# 2_-_IO_Socket_0.net
KiCad netlist of a schematic drawn in Altium Designer
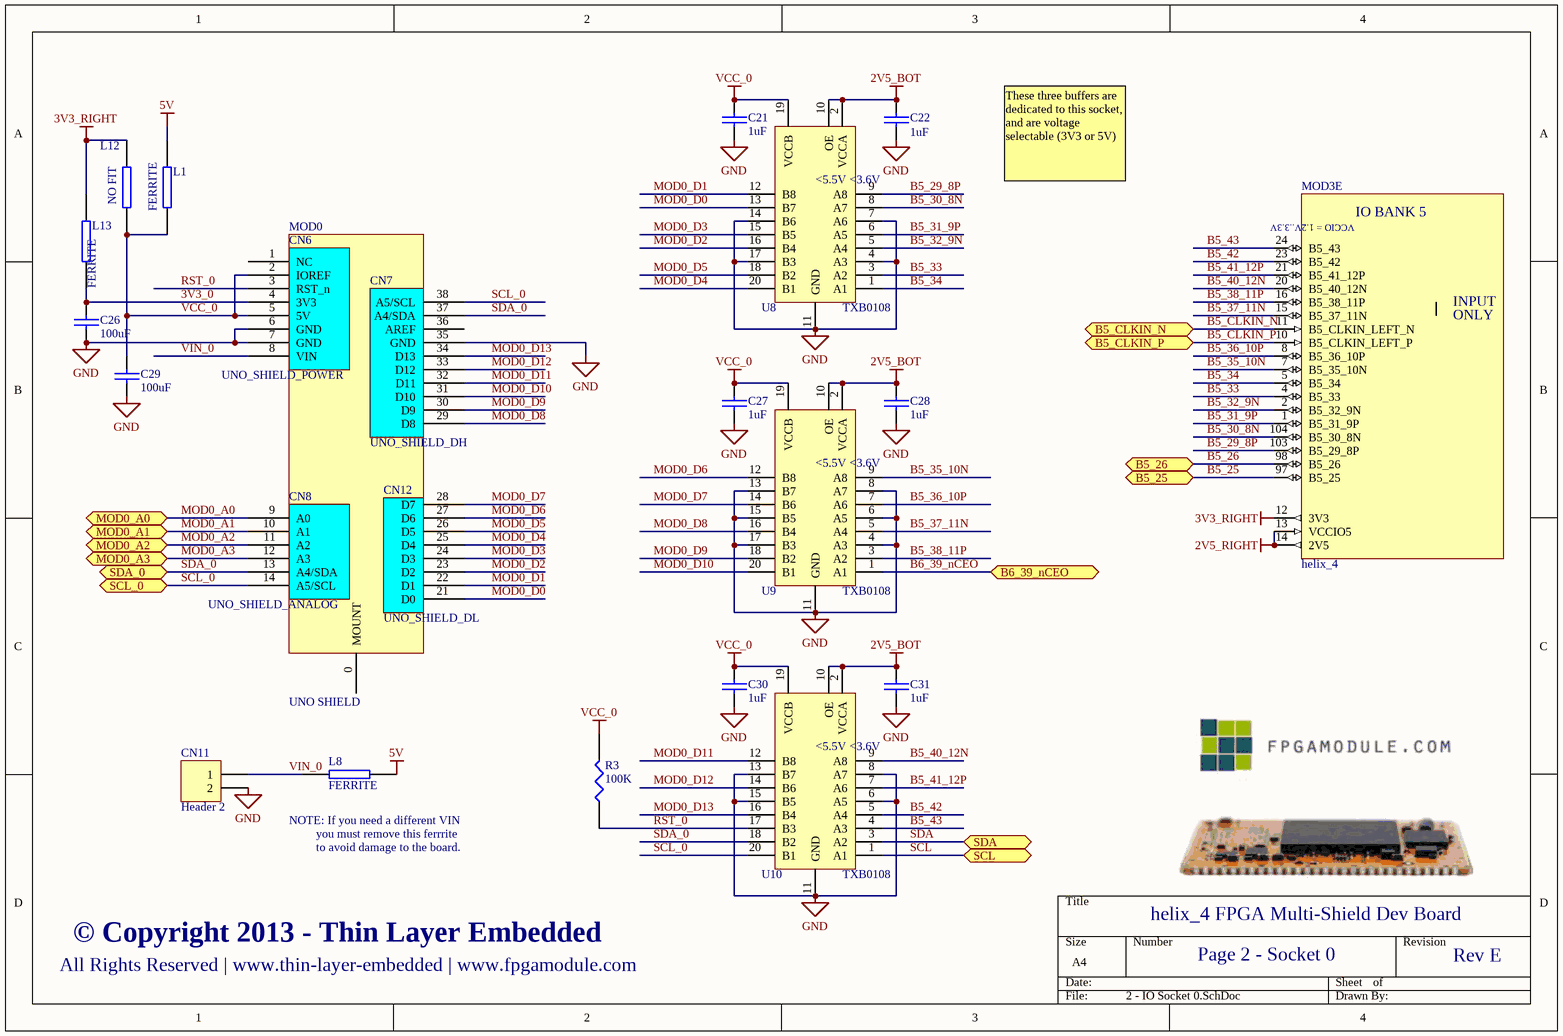
[diagram p0: 2 - IO Socket 0.SchDoc]

(export (version "E")
  (design (tool "Eeschema 10.0.6"))
  (components
    (comp (ref "C21")
      (value "1uF")
      (footprint "0805")
      (description "Capacitor")
      (libsource (lib "*") (part "CAP"))
    )
    (comp (ref "C22")
      (value "1uF")
      (footprint "0805")
      (description "Capacitor")
      (libsource (lib "*") (part "CAP"))
    )
    (comp (ref "C26")
      (value "100uF")
      (footprint "1210")
      (description "Capacitor")
      (libsource (lib "*") (part "CAP"))
    )
    (comp (ref "C27")
      (value "1uF")
      (footprint "0805")
      (description "Capacitor")
      (libsource (lib "*") (part "CAP"))
    )
    (comp (ref "C28")
      (value "1uF")
      (footprint "0805")
      (description "Capacitor")
      (libsource (lib "*") (part "CAP"))
    )
    (comp (ref "C29")
      (value "100uF")
      (footprint "1210")
      (description "Capacitor")
      (libsource (lib "*") (part "CAP"))
    )
    (comp (ref "C30")
      (value "1uF")
      (footprint "0805")
      (description "Capacitor")
      (libsource (lib "*") (part "CAP"))
    )
    (comp (ref "C31")
      (value "1uF")
      (footprint "0805")
      (description "Capacitor")
      (libsource (lib "*") (part "CAP"))
    )
    (comp (ref "CN6")
      (value "UNO_SHIELD_POWER")
      (footprint "UNO_SHIELD_POWER")
      (libsource (lib "master_library") (part "UNO_SHIELD_POWER"))
    )
    (comp (ref "CN7")
      (value "UNO_SHIELD_DH")
      (footprint "UNO_SHIELD_DH")
      (libsource (lib "master_library") (part "UNO_SHIELD_DH"))
    )
    (comp (ref "CN8")
      (value "UNO_SHIELD_ANALOG")
      (footprint "UNO_SHIELD_ANALOG")
      (libsource (lib "master_library") (part "UNO_SHIELD_ANALOG"))
    )
    (comp (ref "CN11")
      (value "Header 2")
      (footprint "HDR1X2")
      (description "Header, 2-Pin")
      (fields (field (name "PUBLISHER") "Altium Limited"))
      (libsource (lib "Miscellaneous Connectors") (part "Header 2"))
    )
    (comp (ref "CN12")
      (value "UNO_SHIELD_DL")
      (footprint "UNO_SHIELD_DL")
      (libsource (lib "master_library") (part "UNO_SHIELD_DL"))
    )
    (comp (ref "L1") (value "FERRITE") (footprint "0805") (libsource (lib "*") (part "FERRITE")))
    (comp (ref "L8") (value "FERRITE") (footprint "0805") (libsource (lib "*") (part "FERRITE")))
    (comp (ref "L12")
      (value "NO FIT")
      (footprint "0805")
      (description "FERRITE")
      (libsource (lib "*") (part "FERRITE"))
    )
    (comp (ref "L13") (value "FERRITE") (footprint "0805") (libsource (lib "*") (part "FERRITE")))
    (comp (ref "MOD0")
      (value "UNO SHIELD")
      (footprint "UNO_SHIELD_MECH")
      (libsource (lib "master_library") (part "UNO_SHIELD_MECH"))
    )
    (comp (ref "MOD3")
      (value "helix_4")
      (footprint "HELIX_4_LCC104_HOST")
      (libsource (lib "master_library") (part "helix_4 Rev C Module"))
    )
    (comp (ref "R3") (value "100K") (footprint "0805") (libsource (lib "*") (part "RES1")))
    (comp (ref "U8")
      (value "TXB0108")
      (footprint "TSSOP20")
      (description "TI Bir-dir buffer")
      (libsource (lib "master_library") (part "TXB0108"))
    )
    (comp (ref "U9")
      (value "TXB0108")
      (footprint "TSSOP20")
      (description "TI Bir-dir buffer")
      (libsource (lib "master_library") (part "TXB0108"))
    )
    (comp (ref "U10")
      (value "TXB0108")
      (footprint "TSSOP20")
      (description "TI Bir-dir buffer")
      (libsource (lib "master_library") (part "TXB0108"))
    )
  )
  (nets
    (net (code "1") (name "/3V3_0") (class "Default")
      (node (ref "C26") (pin "1") (pinfunction "1_1") (pintype "passive"))
      (node (ref "CN6") (pin "4") (pinfunction "3V3_4") (pintype "passive"))
      (node (ref "L13") (pin "2") (pinfunction "2_2") (pintype "passive"))
    )
    (net (code "2") (name "/B5_25") (class "Default")
      (node (ref "MOD3") (pin "97") (pinfunction "B5_25_97") (pintype "bidirectional"))
    )
    (net (code "3") (name "/B5_26") (class "Default")
      (node (ref "MOD3") (pin "98") (pinfunction "B5_26_98") (pintype "bidirectional"))
    )
    (net (code "4") (name "/B5_29_8P") (class "Default")
      (node (ref "MOD3") (pin "103") (pinfunction "B5_29_8P_103") (pintype "bidirectional"))
      (node (ref "U8") (pin "9") (pinfunction "A8_9") (pintype "passive"))
    )
    (net (code "5") (name "/B5_30_8N") (class "Default")
      (node (ref "MOD3") (pin "104") (pinfunction "B5_30_8N_104") (pintype "bidirectional"))
      (node (ref "U8") (pin "8") (pinfunction "A7_8") (pintype "passive"))
    )
    (net (code "6") (name "/B5_31_9P") (class "Default")
      (node (ref "MOD3") (pin "1") (pinfunction "B5_31_9P_1") (pintype "bidirectional"))
      (node (ref "U8") (pin "6") (pinfunction "A5_6") (pintype "passive"))
    )
    (net (code "7") (name "/B5_32_9N") (class "Default")
      (node (ref "MOD3") (pin "2") (pinfunction "B5_32_9N_2") (pintype "bidirectional"))
      (node (ref "U8") (pin "5") (pinfunction "A4_5") (pintype "passive"))
    )
    (net (code "8") (name "/B5_33") (class "Default")
      (node (ref "MOD3") (pin "4") (pinfunction "B5_33_4") (pintype "bidirectional"))
      (node (ref "U8") (pin "3") (pinfunction "A2_3") (pintype "passive"))
    )
    (net (code "9") (name "/B5_34") (class "Default")
      (node (ref "MOD3") (pin "5") (pinfunction "B5_34_5") (pintype "bidirectional"))
      (node (ref "U8") (pin "1") (pinfunction "A1_1") (pintype "passive"))
    )
    (net (code "10") (name "/B5_35_10N") (class "Default")
      (node (ref "MOD3") (pin "7") (pinfunction "B5_35_10N_7") (pintype "bidirectional"))
      (node (ref "U9") (pin "9") (pinfunction "A8_9") (pintype "passive"))
    )
    (net (code "11") (name "/B5_36_10P") (class "Default")
      (node (ref "MOD3") (pin "8") (pinfunction "B5_36_10P_8") (pintype "bidirectional"))
      (node (ref "U9") (pin "7") (pinfunction "A6_7") (pintype "passive"))
    )
    (net (code "12") (name "/B5_37_11N") (class "Default")
      (node (ref "MOD3") (pin "15") (pinfunction "B5_37_11N_15") (pintype "bidirectional"))
      (node (ref "U9") (pin "5") (pinfunction "A4_5") (pintype "passive"))
    )
    (net (code "13") (name "/B5_38_11P") (class "Default")
      (node (ref "MOD3") (pin "16") (pinfunction "B5_38_11P_16") (pintype "bidirectional"))
      (node (ref "U9") (pin "3") (pinfunction "A2_3") (pintype "passive"))
    )
    (net (code "14") (name "/B5_40_12N") (class "Default")
      (node (ref "MOD3") (pin "20") (pinfunction "B5_40_12N_20") (pintype "bidirectional"))
      (node (ref "U10") (pin "9") (pinfunction "A8_9") (pintype "passive"))
    )
    (net (code "15") (name "/B5_41_12P") (class "Default")
      (node (ref "MOD3") (pin "21") (pinfunction "B5_41_12P_21") (pintype "bidirectional"))
      (node (ref "U10") (pin "7") (pinfunction "A6_7") (pintype "passive"))
    )
    (net (code "16") (name "/B5_42") (class "Default")
      (node (ref "MOD3") (pin "23") (pinfunction "B5_42_23") (pintype "bidirectional"))
      (node (ref "U10") (pin "5") (pinfunction "A4_5") (pintype "passive"))
    )
    (net (code "17") (name "/B5_43") (class "Default")
      (node (ref "MOD3") (pin "24") (pinfunction "B5_43_24") (pintype "bidirectional"))
      (node (ref "U10") (pin "4") (pinfunction "A3_4") (pintype "passive"))
    )
    (net (code "18") (name "/B5_CLKIN_N") (class "Default")
      (node (ref "MOD3") (pin "11") (pinfunction "B5_CLKIN_LEFT_N_11") (pintype "input"))
    )
    (net (code "19") (name "/B5_CLKIN_P") (class "Default")
      (node (ref "MOD3") (pin "10") (pinfunction "B5_CLKIN_LEFT_P_10") (pintype "input"))
    )
    (net (code "20") (name "/B6_39_nCEO") (class "Default")
      (node (ref "U9") (pin "1") (pinfunction "A1_1") (pintype "passive"))
    )
    (net (code "21") (name "/MOD0_A0") (class "Default")
      (node (ref "CN8") (pin "9") (pinfunction "A0_9") (pintype "passive"))
    )
    (net (code "22") (name "/MOD0_A1") (class "Default")
      (node (ref "CN8") (pin "10") (pinfunction "A1_10") (pintype "passive"))
    )
    (net (code "23") (name "/MOD0_A2") (class "Default")
      (node (ref "CN8") (pin "11") (pinfunction "A2_11") (pintype "passive"))
    )
    (net (code "24") (name "/MOD0_A3") (class "Default")
      (node (ref "CN8") (pin "12") (pinfunction "A3_12") (pintype "passive"))
    )
    (net (code "25") (name "/MOD0_D0") (class "Default")
      (node (ref "CN12") (pin "21") (pinfunction "D0_21") (pintype "passive"))
      (node (ref "U8") (pin "13") (pinfunction "B7_13") (pintype "passive"))
    )
    (net (code "26") (name "/MOD0_D1") (class "Default")
      (node (ref "CN12") (pin "22") (pinfunction "D1_22") (pintype "passive"))
      (node (ref "U8") (pin "12") (pinfunction "B8_12") (pintype "passive"))
    )
    (net (code "27") (name "/MOD0_D2") (class "Default")
      (node (ref "CN12") (pin "23") (pinfunction "D2_23") (pintype "passive"))
      (node (ref "U8") (pin "16") (pinfunction "B4_16") (pintype "passive"))
    )
    (net (code "28") (name "/MOD0_D3") (class "Default")
      (node (ref "CN12") (pin "24") (pinfunction "D3_24") (pintype "passive"))
      (node (ref "U8") (pin "15") (pinfunction "B5_15") (pintype "passive"))
    )
    (net (code "29") (name "/MOD0_D4") (class "Default")
      (node (ref "CN12") (pin "25") (pinfunction "D4_25") (pintype "passive"))
      (node (ref "U8") (pin "20") (pinfunction "B1_20") (pintype "passive"))
    )
    (net (code "30") (name "/MOD0_D5") (class "Default")
      (node (ref "CN12") (pin "26") (pinfunction "D5_26") (pintype "passive"))
      (node (ref "U8") (pin "18") (pinfunction "B2_18") (pintype "passive"))
    )
    (net (code "31") (name "/MOD0_D6") (class "Default")
      (node (ref "CN12") (pin "27") (pinfunction "D6_27") (pintype "passive"))
      (node (ref "U9") (pin "12") (pinfunction "B8_12") (pintype "passive"))
    )
    (net (code "32") (name "/MOD0_D7") (class "Default")
      (node (ref "CN12") (pin "28") (pinfunction "D7_28") (pintype "passive"))
      (node (ref "U9") (pin "14") (pinfunction "B6_14") (pintype "passive"))
    )
    (net (code "33") (name "/MOD0_D8") (class "Default")
      (node (ref "CN7") (pin "29") (pinfunction "D8_29") (pintype "passive"))
      (node (ref "U9") (pin "16") (pinfunction "B4_16") (pintype "passive"))
    )
    (net (code "34") (name "/MOD0_D9") (class "Default")
      (node (ref "CN7") (pin "30") (pinfunction "D9_30") (pintype "passive"))
      (node (ref "U9") (pin "18") (pinfunction "B2_18") (pintype "passive"))
    )
    (net (code "35") (name "/MOD0_D10") (class "Default")
      (node (ref "CN7") (pin "31") (pinfunction "D10_31") (pintype "passive"))
      (node (ref "U9") (pin "20") (pinfunction "B1_20") (pintype "passive"))
    )
    (net (code "36") (name "/MOD0_D11") (class "Default")
      (node (ref "CN7") (pin "32") (pinfunction "D11_32") (pintype "passive"))
      (node (ref "U10") (pin "12") (pinfunction "B8_12") (pintype "passive"))
    )
    (net (code "37") (name "/MOD0_D12") (class "Default")
      (node (ref "CN7") (pin "33") (pinfunction "D12_33") (pintype "passive"))
      (node (ref "U10") (pin "14") (pinfunction "B6_14") (pintype "passive"))
    )
    (net (code "38") (name "/MOD0_D13") (class "Default")
      (node (ref "CN7") (pin "34") (pinfunction "D13_34") (pintype "passive"))
      (node (ref "U10") (pin "16") (pinfunction "B4_16") (pintype "passive"))
    )
    (net (code "39") (name "/RST_0") (class "Default")
      (node (ref "CN6") (pin "3") (pinfunction "RST_n_3") (pintype "passive"))
      (node (ref "R3") (pin "1") (pinfunction "1_1") (pintype "passive"))
      (node (ref "U10") (pin "17") (pinfunction "B3_17") (pintype "passive"))
    )
    (net (code "40") (name "/SCL") (class "Default")
      (node (ref "U10") (pin "1") (pinfunction "A1_1") (pintype "passive"))
    )
    (net (code "41") (name "/SCL_0") (class "Default")
      (node (ref "CN7") (pin "38") (pinfunction "A5/SCL_38") (pintype "passive"))
      (node (ref "CN8") (pin "14") (pinfunction "A5/SCL_14") (pintype "passive"))
      (node (ref "U10") (pin "20") (pinfunction "B1_20") (pintype "passive"))
    )
    (net (code "42") (name "/SDA") (class "Default")
      (node (ref "U10") (pin "3") (pinfunction "A2_3") (pintype "passive"))
    )
    (net (code "43") (name "/SDA_0") (class "Default")
      (node (ref "CN7") (pin "37") (pinfunction "A4/SDA_37") (pintype "passive"))
      (node (ref "CN8") (pin "13") (pinfunction "A4/SDA_13") (pintype "passive"))
      (node (ref "U10") (pin "18") (pinfunction "B2_18") (pintype "passive"))
    )
    (net (code "44") (name "/VIN_0") (class "Default")
      (node (ref "CN11") (pin "1") (pinfunction "1_1") (pintype "passive"))
      (node (ref "CN6") (pin "8") (pinfunction "VIN_8") (pintype "passive"))
      (node (ref "L8") (pin "2") (pinfunction "2_2") (pintype "passive"))
    )
    (net (code "45") (name "2V5_BOT") (class "Default")
      (node (ref "C22") (pin "2") (pinfunction "2_2") (pintype "passive"))
      (node (ref "C28") (pin "2") (pinfunction "2_2") (pintype "passive"))
      (node (ref "C31") (pin "2") (pinfunction "2_2") (pintype "passive"))
      (node (ref "U10") (pin "10") (pinfunction "OE_10") (pintype "passive"))
      (node (ref "U10") (pin "2") (pinfunction "VCCA_2") (pintype "passive"))
      (node (ref "U8") (pin "10") (pinfunction "OE_10") (pintype "passive"))
      (node (ref "U8") (pin "2") (pinfunction "VCCA_2") (pintype "passive"))
      (node (ref "U9") (pin "10") (pinfunction "OE_10") (pintype "passive"))
      (node (ref "U9") (pin "2") (pinfunction "VCCA_2") (pintype "passive"))
    )
    (net (code "46") (name "2V5_RIGHT") (class "Default")
      (node (ref "MOD3") (pin "13") (pinfunction "VCCIO5_13") (pintype "input"))
      (node (ref "MOD3") (pin "14") (pinfunction "2V5_14") (pintype "output"))
    )
    (net (code "47") (name "3V3_RIGHT") (class "Default")
      (node (ref "L12") (pin "1") (pinfunction "1_1") (pintype "passive"))
      (node (ref "L13") (pin "1") (pinfunction "1_1") (pintype "passive"))
      (node (ref "MOD3") (pin "12") (pinfunction "3V3_12") (pintype "output"))
    )
    (net (code "48") (name "5V") (class "Default")
      (node (ref "L1") (pin "1") (pinfunction "1_1") (pintype "passive"))
      (node (ref "L8") (pin "1") (pinfunction "1_1") (pintype "passive"))
    )
    (net (code "49") (name "GND") (class "Default")
      (node (ref "C21") (pin "1") (pinfunction "1_1") (pintype "passive"))
      (node (ref "C22") (pin "1") (pinfunction "1_1") (pintype "passive"))
      (node (ref "C26") (pin "2") (pinfunction "2_2") (pintype "passive"))
      (node (ref "C27") (pin "1") (pinfunction "1_1") (pintype "passive"))
      (node (ref "C28") (pin "1") (pinfunction "1_1") (pintype "passive"))
      (node (ref "C29") (pin "2") (pinfunction "2_2") (pintype "passive"))
      (node (ref "C30") (pin "1") (pinfunction "1_1") (pintype "passive"))
      (node (ref "C31") (pin "1") (pinfunction "1_1") (pintype "passive"))
      (node (ref "CN11") (pin "2") (pinfunction "2_2") (pintype "passive"))
      (node (ref "CN6") (pin "6") (pinfunction "GND_6") (pintype "passive"))
      (node (ref "CN6") (pin "7") (pinfunction "GND_7") (pintype "passive"))
      (node (ref "CN7") (pin "35") (pinfunction "GND_35") (pintype "passive"))
      (node (ref "U10") (pin "11") (pinfunction "GND_11") (pintype "passive"))
      (node (ref "U10") (pin "13") (pinfunction "B7_13") (pintype "passive"))
      (node (ref "U10") (pin "15") (pinfunction "B5_15") (pintype "passive"))
      (node (ref "U10") (pin "6") (pinfunction "A5_6") (pintype "passive"))
      (node (ref "U10") (pin "8") (pinfunction "A7_8") (pintype "passive"))
      (node (ref "U8") (pin "11") (pinfunction "GND_11") (pintype "passive"))
      (node (ref "U8") (pin "14") (pinfunction "B6_14") (pintype "passive"))
      (node (ref "U8") (pin "17") (pinfunction "B3_17") (pintype "passive"))
      (node (ref "U8") (pin "4") (pinfunction "A3_4") (pintype "passive"))
      (node (ref "U8") (pin "7") (pinfunction "A6_7") (pintype "passive"))
      (node (ref "U9") (pin "11") (pinfunction "GND_11") (pintype "passive"))
      (node (ref "U9") (pin "13") (pinfunction "B7_13") (pintype "passive"))
      (node (ref "U9") (pin "15") (pinfunction "B5_15") (pintype "passive"))
      (node (ref "U9") (pin "17") (pinfunction "B3_17") (pintype "passive"))
      (node (ref "U9") (pin "4") (pinfunction "A3_4") (pintype "passive"))
      (node (ref "U9") (pin "6") (pinfunction "A5_6") (pintype "passive"))
      (node (ref "U9") (pin "8") (pinfunction "A7_8") (pintype "passive"))
    )
    (net (code "50") (name "VCC_0") (class "Default")
      (node (ref "C21") (pin "2") (pinfunction "2_2") (pintype "passive"))
      (node (ref "C27") (pin "2") (pinfunction "2_2") (pintype "passive"))
      (node (ref "C29") (pin "1") (pinfunction "1_1") (pintype "passive"))
      (node (ref "C30") (pin "2") (pinfunction "2_2") (pintype "passive"))
      (node (ref "CN6") (pin "2") (pinfunction "IOREF_2") (pintype "passive"))
      (node (ref "CN6") (pin "5") (pinfunction "5V_5") (pintype "passive"))
      (node (ref "L1") (pin "2") (pinfunction "2_2") (pintype "passive"))
      (node (ref "L12") (pin "2") (pinfunction "2_2") (pintype "passive"))
      (node (ref "R3") (pin "2") (pinfunction "2_2") (pintype "passive"))
      (node (ref "U10") (pin "19") (pinfunction "VCCB_19") (pintype "passive"))
      (node (ref "U8") (pin "19") (pinfunction "VCCB_19") (pintype "passive"))
      (node (ref "U9") (pin "19") (pinfunction "VCCB_19") (pintype "passive"))
    )
    (net (code "51") (name "unconnected-(CN6-NC-Pad1)") (class "Default")
      (node (ref "CN6") (pin "1") (pinfunction "NC_1") (pintype "passive"))
    )
    (net (code "52") (name "unconnected-(CN7-AREF-Pad36)") (class "Default")
      (node (ref "CN7") (pin "36") (pinfunction "AREF_36") (pintype "passive"))
    )
    (net (code "53") (name "unconnected-(MOD0-MOUNT-Pad0)") (class "Default")
      (node (ref "MOD0") (pin "0") (pinfunction "MOUNT_0") (pintype "passive"))
    )
  )
)
